# Smart_Umbrella.net
KiCad netlist of a schematic drawn in Altium Designer
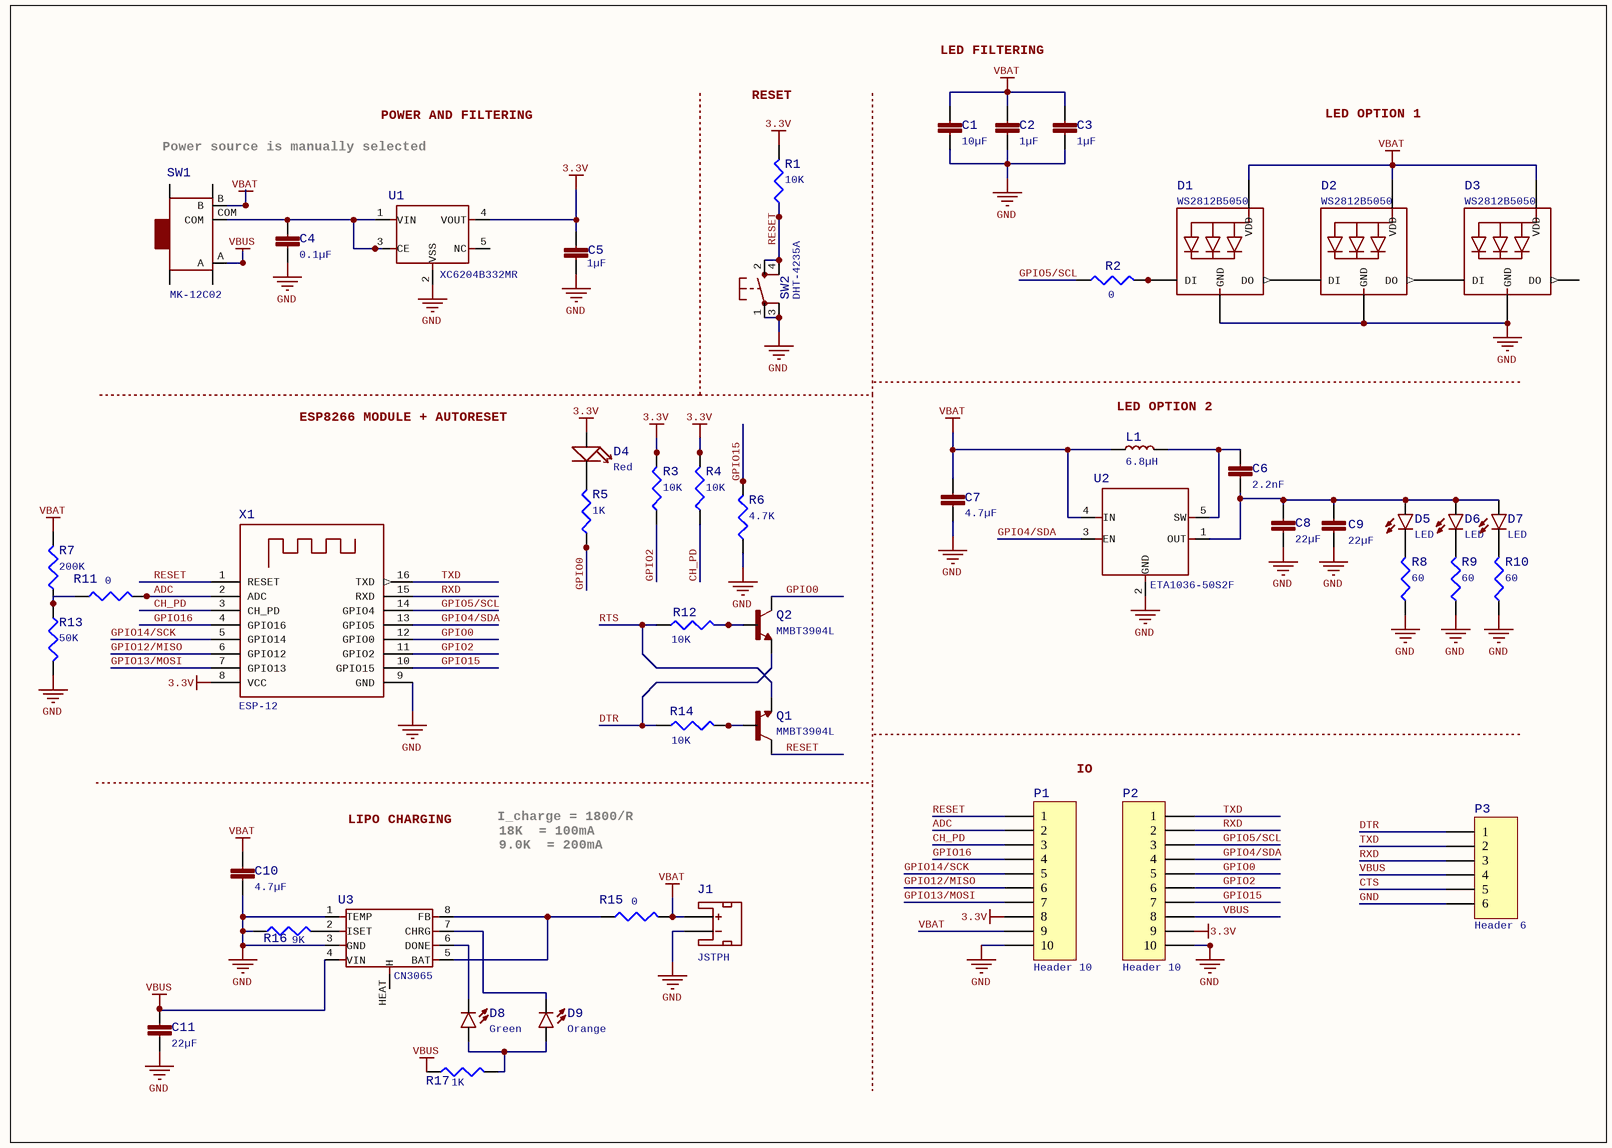
[diagram p0: Smart_Umbrella.SchDoc]

(export (version "E")
  (design (tool "Eeschema 10.0.6"))
  (components
    (comp (ref "C1")
      (value "10µF")
      (footprint "0805")
      (libsource (lib "SparkFun-Capacitors") (part "10UF-0805-10V-10%"))
    )
    (comp (ref "C2")
      (value "1µF")
      (footprint "0603")
      (libsource (lib "SparkFun-Capacitors") (part "1.0UF-0603-16V-10%"))
    )
    (comp (ref "C3")
      (value "1µF")
      (footprint "0603")
      (libsource (lib "SparkFun-Capacitors") (part "1.0UF-0603-16V-10%"))
    )
    (comp (ref "C4")
      (value "0.1µF")
      (footprint "0805")
      (libsource (lib "SparkFun-Capacitors") (part "10UF-0805-10V-10%"))
    )
    (comp (ref "C5")
      (value "1µF")
      (footprint "0603")
      (libsource (lib "SparkFun-Capacitors") (part "1.0UF-0603-16V-10%"))
    )
    (comp (ref "C6")
      (value "2.2nF")
      (footprint "0603")
      (libsource (lib "SparkFun-Capacitors") (part "1.0UF-0603-16V-10%"))
    )
    (comp (ref "C7")
      (value "4.7µF")
      (footprint "0805")
      (libsource (lib "SparkFun-Capacitors") (part "10UF-0805-10V-10%"))
    )
    (comp (ref "C8")
      (value "22µF")
      (footprint "0805")
      (libsource (lib "SparkFun-Capacitors") (part "10UF-0805-10V-10%"))
    )
    (comp (ref "C9")
      (value "22µF")
      (footprint "0805")
      (libsource (lib "SparkFun-Capacitors") (part "10UF-0805-10V-10%"))
    )
    (comp (ref "C10")
      (value "4.7µF")
      (footprint "0805")
      (libsource (lib "SparkFun-Capacitors") (part "10UF-0805-10V-10%"))
    )
    (comp (ref "C11")
      (value "22µF")
      (footprint "0805")
      (libsource (lib "SparkFun-Capacitors") (part "10UF-0805-10V-10%"))
    )
    (comp (ref "D1")
      (value "WS2812B5050")
      (footprint "WS2812B")
      (libsource (lib "adafruit") (part "WS2812B5050"))
    )
    (comp (ref "D2")
      (value "WS2812B5050")
      (footprint "WS2812B")
      (libsource (lib "adafruit") (part "WS2812B5050"))
    )
    (comp (ref "D3")
      (value "WS2812B5050")
      (footprint "WS2812B")
      (libsource (lib "adafruit") (part "WS2812B5050"))
    )
    (comp (ref "D4") (value "Red") (footprint "LED-0603") (libsource (lib "Discrete") (part "LED-0603")))
    (comp (ref "D5") (value "LED") (footprint "LED_5MM") (libsource (lib "SparkFun-LED") (part "LED5MM")))
    (comp (ref "D6") (value "LED") (footprint "LED_5MM") (libsource (lib "SparkFun-LED") (part "LED5MM")))
    (comp (ref "D7") (value "LED") (footprint "LED_5MM") (libsource (lib "SparkFun-LED") (part "LED5MM")))
    (comp (ref "D8")
      (value "Green")
      (footprint "LED-0603")
      (libsource (lib "SparkFun-LED") (part "LED-RED0603"))
    )
    (comp (ref "D9")
      (value "Orange")
      (footprint "LED-0603")
      (libsource (lib "SparkFun-LED") (part "LED-RED0603"))
    )
    (comp (ref "J1")
      (value "JSTPH")
      (footprint "JST-2-SMD")
      (libsource (lib "SparkFun-Connectors") (part "JST_2MM_MALE"))
    )
    (comp (ref "L1")
      (value "6.8µH")
      (footprint "L0603")
      (libsource (lib "Discrete") (part "INDUCTOR/FERRITE-BEAD-0603"))
    )
    (comp (ref "P1")
      (value "Header 10")
      (footprint "HDR1X10")
      (description "Header, 10-Pin")
      (fields (field (name "PUBLISHER") "Altium Limited"))
      (libsource (lib "Miscellaneous Connectors") (part "Header 10"))
    )
    (comp (ref "P2")
      (value "Header 10")
      (footprint "HDR1X10")
      (description "Header, 10-Pin")
      (fields (field (name "PUBLISHER") "Altium Limited"))
      (libsource (lib "") (part "Header 10_1"))
    )
    (comp (ref "P3")
      (value "Header 6")
      (footprint "HDR1X6")
      (description "Header, 6-Pin")
      (fields (field (name "PUBLISHER") "Altium Limited"))
      (libsource (lib "Miscellaneous Connectors") (part "Header 6"))
    )
    (comp (ref "Q1")
      (value "MMBT3904L")
      (footprint "SOT23-3")
      (fields (field (name "DRAWN") "KTOWN"))
      (libsource (lib "SparkFun") (part "TRANSISTOR_NPNSOT23-3"))
    )
    (comp (ref "Q2")
      (value "MMBT3904L")
      (footprint "SOT23-3")
      (fields (field (name "DRAWN") "KTOWN"))
      (libsource (lib "") (part "TRANSISTOR_NPNSOT23-3_1"))
    )
    (comp (ref "R1")
      (value "10K")
      (footprint "J1-0603")
      (description "Resistor")
      (fields (field (name "Comment") "Res3") (field (name "PUBLISHER") "Altium Limited"))
      (libsource (lib "Miscellaneous Devices") (part "Res3"))
    )
    (comp (ref "R2")
      (value "0")
      (footprint "J1-0603")
      (description "Resistor")
      (fields (field (name "Comment") "Res3") (field (name "PUBLISHER") "Altium Limited"))
      (libsource (lib "Miscellaneous Devices") (part "Res3"))
    )
    (comp (ref "R3")
      (value "10K")
      (footprint "J1-0603")
      (description "Resistor")
      (fields (field (name "Comment") "Res3") (field (name "PUBLISHER") "Altium Limited"))
      (libsource (lib "Miscellaneous Devices") (part "Res3"))
    )
    (comp (ref "R4")
      (value "10K")
      (footprint "J1-0603")
      (description "Resistor")
      (fields (field (name "Comment") "Res3") (field (name "PUBLISHER") "Altium Limited"))
      (libsource (lib "Miscellaneous Devices") (part "Res3"))
    )
    (comp (ref "R5")
      (value "1K")
      (footprint "J1-0603")
      (description "Resistor")
      (fields (field (name "Comment") "Res3") (field (name "PUBLISHER") "Altium Limited"))
      (libsource (lib "Miscellaneous Devices") (part "Res3"))
    )
    (comp (ref "R6")
      (value "4.7K")
      (footprint "J1-0603")
      (description "Resistor")
      (fields (field (name "Comment") "Res3") (field (name "PUBLISHER") "Altium Limited"))
      (libsource (lib "Miscellaneous Devices") (part "Res3"))
    )
    (comp (ref "R7")
      (value "200K")
      (footprint "J1-0603")
      (description "Resistor")
      (fields (field (name "Comment") "Res3") (field (name "PUBLISHER") "Altium Limited"))
      (libsource (lib "Miscellaneous Devices") (part "Res3"))
    )
    (comp (ref "R8")
      (value "60")
      (footprint "J1-0603")
      (description "Resistor")
      (fields (field (name "Comment") "Res3") (field (name "PUBLISHER") "Altium Limited"))
      (libsource (lib "Miscellaneous Devices") (part "Res3"))
    )
    (comp (ref "R9")
      (value "60")
      (footprint "J1-0603")
      (description "Resistor")
      (fields (field (name "Comment") "Res3") (field (name "PUBLISHER") "Altium Limited"))
      (libsource (lib "Miscellaneous Devices") (part "Res3"))
    )
    (comp (ref "R10")
      (value "60")
      (footprint "J1-0603")
      (description "Resistor")
      (fields (field (name "Comment") "Res3") (field (name "PUBLISHER") "Altium Limited"))
      (libsource (lib "Miscellaneous Devices") (part "Res3"))
    )
    (comp (ref "R11")
      (value "0")
      (footprint "J1-0603")
      (description "Resistor")
      (fields (field (name "Comment") "Res3") (field (name "PUBLISHER") "Altium Limited"))
      (libsource (lib "Miscellaneous Devices") (part "Res3"))
    )
    (comp (ref "R12")
      (value "10K")
      (footprint "J1-0603")
      (description "Resistor")
      (fields (field (name "Comment") "Res3") (field (name "PUBLISHER") "Altium Limited"))
      (libsource (lib "Miscellaneous Devices") (part "Res3"))
    )
    (comp (ref "R13")
      (value "50K")
      (footprint "J1-0603")
      (description "Resistor")
      (fields (field (name "Comment") "Res3") (field (name "PUBLISHER") "Altium Limited"))
      (libsource (lib "Miscellaneous Devices") (part "Res3"))
    )
    (comp (ref "R14")
      (value "10K")
      (footprint "J1-0603")
      (description "Resistor")
      (fields (field (name "Comment") "Res3") (field (name "PUBLISHER") "Altium Limited"))
      (libsource (lib "Miscellaneous Devices") (part "Res3"))
    )
    (comp (ref "R15")
      (value "0")
      (footprint "J1-0603")
      (description "Resistor")
      (fields (field (name "Comment") "Res3") (field (name "PUBLISHER") "Altium Limited"))
      (libsource (lib "Miscellaneous Devices") (part "Res3"))
    )
    (comp (ref "R16")
      (value "9K")
      (footprint "J1-0603")
      (description "Resistor")
      (fields (field (name "Comment") "Res3") (field (name "PUBLISHER") "Altium Limited"))
      (libsource (lib "Miscellaneous Devices") (part "Res3"))
    )
    (comp (ref "R17")
      (value "1K")
      (footprint "J1-0603")
      (description "Resistor")
      (fields (field (name "Comment") "Res3") (field (name "PUBLISHER") "Altium Limited"))
      (libsource (lib "Miscellaneous Devices") (part "Res3"))
    )
    (comp (ref "SW1")
      (value "MK-12C02")
      (footprint "SW7-SMD-L6.7X2.7X3.2MM")
      (libsource (lib "Seeed-OPL-Button") (part "SMD-TOGGLE-SWITCH-ON-ON(3+4P-6.7X2.7MM)"))
    )
    (comp (ref "SW2")
      (value "DHT-4235A")
      (footprint "KMR2")
      (libsource (lib "adafruit") (part "SPST_TACT-KMR2"))
    )
    (comp (ref "U1")
      (value "XC6204B332MR")
      (footprint "SOT-23-5")
      (libsource (lib "Seeed-OPL-ic") (part "PMIC-LDO-XC6204B332MR(SOT23-5)"))
    )
    (comp (ref "U2")
      (value "ETA1036-50S2F")
      (footprint "SOT-23-5")
      (fields (field (name "MPN") "ETA1036-50S2F-T"))
      (libsource (lib "Seeed-OPL-ic") (part "PMIC-ETA1036-50S2F-T(SOT23-5)"))
    )
    (comp (ref "U3")
      (value "CN3065")
      (footprint "DFN8G-0.5-3X3MM")
      (libsource (lib "Seeed-OPL-ic") (part "PMIC-CN3065(DFN8)"))
    )
    (comp (ref "X1") (value "ESP-12") (footprint "ESP-12") (libsource (lib "adafruit") (part "ESP-12")))
  )
  (nets
    (net (code "1") (name "/ADC") (class "Default")
      (node (ref "P1") (pin "2") (pinfunction "2_2") (pintype "passive"))
      (node (ref "R11") (pin "2") (pinfunction "2_2") (pintype "passive"))
      (node (ref "X1") (pin "2") (pinfunction "ADC_2") (pintype "passive"))
    )
    (net (code "2") (name "/CH_PD") (class "Default")
      (node (ref "P1") (pin "3") (pinfunction "3_3") (pintype "passive"))
      (node (ref "R4") (pin "1") (pinfunction "1_1") (pintype "passive"))
      (node (ref "X1") (pin "3") (pinfunction "CH_PD_3") (pintype "passive"))
    )
    (net (code "3") (name "/CTS") (class "Default")
      (node (ref "P3") (pin "5") (pinfunction "5_5") (pintype "passive"))
    )
    (net (code "4") (name "/DTR") (class "Default")
      (node (ref "P3") (pin "1") (pinfunction "1_1") (pintype "passive"))
      (node (ref "Q2") (pin "2") (pinfunction "E_2") (pintype "passive"))
      (node (ref "R14") (pin "1") (pinfunction "1_1") (pintype "passive"))
    )
    (net (code "5") (name "/GPIO0") (class "Default")
      (node (ref "P2") (pin "5") (pinfunction "5_5") (pintype "passive"))
      (node (ref "Q2") (pin "3") (pinfunction "C_3") (pintype "passive"))
      (node (ref "R5") (pin "1") (pinfunction "1_1") (pintype "passive"))
      (node (ref "X1") (pin "12") (pinfunction "GPIO0_12") (pintype "passive"))
    )
    (net (code "6") (name "/GPIO2") (class "Default")
      (node (ref "P2") (pin "6") (pinfunction "6_6") (pintype "passive"))
      (node (ref "R3") (pin "1") (pinfunction "1_1") (pintype "passive"))
      (node (ref "X1") (pin "11") (pinfunction "GPIO2_11") (pintype "passive"))
    )
    (net (code "7") (name "/GPIO4{slash}SDA") (class "Default")
      (node (ref "P2") (pin "4") (pinfunction "4_4") (pintype "passive"))
      (node (ref "U2") (pin "3") (pinfunction "EN_3") (pintype "passive"))
      (node (ref "X1") (pin "13") (pinfunction "GPIO5_13") (pintype "passive"))
    )
    (net (code "8") (name "/GPIO5{slash}SCL") (class "Default")
      (node (ref "P2") (pin "3") (pinfunction "3_3") (pintype "passive"))
      (node (ref "R2") (pin "1") (pinfunction "1_1") (pintype "passive"))
      (node (ref "X1") (pin "14") (pinfunction "GPIO4_14") (pintype "passive"))
    )
    (net (code "9") (name "/GPIO12{slash}MISO") (class "Default")
      (node (ref "P1") (pin "6") (pinfunction "6_6") (pintype "passive"))
      (node (ref "X1") (pin "6") (pinfunction "GPIO12_6") (pintype "passive"))
    )
    (net (code "10") (name "/GPIO13{slash}MOSI") (class "Default")
      (node (ref "P1") (pin "7") (pinfunction "7_7") (pintype "passive"))
      (node (ref "X1") (pin "7") (pinfunction "GPIO13_7") (pintype "passive"))
    )
    (net (code "11") (name "/GPIO14{slash}SCK") (class "Default")
      (node (ref "P1") (pin "5") (pinfunction "5_5") (pintype "passive"))
      (node (ref "X1") (pin "5") (pinfunction "GPIO14_5") (pintype "passive"))
    )
    (net (code "12") (name "/GPIO15") (class "Default")
      (node (ref "P2") (pin "7") (pinfunction "7_7") (pintype "passive"))
      (node (ref "R6") (pin "2") (pinfunction "2_2") (pintype "passive"))
      (node (ref "X1") (pin "10") (pinfunction "GPIO15_10") (pintype "passive"))
    )
    (net (code "13") (name "/GPIO16") (class "Default")
      (node (ref "P1") (pin "4") (pinfunction "4_4") (pintype "passive"))
      (node (ref "X1") (pin "4") (pinfunction "GPIO16_4") (pintype "passive"))
    )
    (net (code "14") (name "/RESET") (class "Default")
      (node (ref "P1") (pin "1") (pinfunction "1_1") (pintype "passive"))
      (node (ref "Q1") (pin "3") (pinfunction "C_3") (pintype "passive"))
      (node (ref "R1") (pin "1") (pinfunction "1_1") (pintype "passive"))
      (node (ref "SW2") (pin "2") (pinfunction "S_2") (pintype "passive"))
      (node (ref "SW2") (pin "4") (pinfunction "S1_4") (pintype "passive"))
      (node (ref "X1") (pin "1") (pinfunction "RESET_1") (pintype "passive"))
    )
    (net (code "15") (name "/RTS") (class "Default")
      (node (ref "Q1") (pin "2") (pinfunction "E_2") (pintype "passive"))
      (node (ref "R12") (pin "1") (pinfunction "1_1") (pintype "passive"))
    )
    (net (code "16") (name "/RXD") (class "Default")
      (node (ref "P2") (pin "2") (pinfunction "2_2") (pintype "passive"))
      (node (ref "P3") (pin "3") (pinfunction "3_3") (pintype "passive"))
      (node (ref "X1") (pin "15") (pinfunction "RXD_15") (pintype "passive"))
    )
    (net (code "17") (name "/TXD") (class "Default")
      (node (ref "P2") (pin "1") (pinfunction "1_1") (pintype "passive"))
      (node (ref "P3") (pin "2") (pinfunction "2_2") (pintype "passive"))
      (node (ref "X1") (pin "16") (pinfunction "TXD_16") (pintype "output"))
    )
    (net (code "18") (name "3.3V") (class "Default")
      (node (ref "C5") (pin "1") (pinfunction "1_1") (pintype "passive"))
      (node (ref "D4") (pin "+") (pinfunction "+_+") (pintype "passive"))
      (node (ref "P1") (pin "8") (pinfunction "8_8") (pintype "passive"))
      (node (ref "P2") (pin "9") (pinfunction "9_9") (pintype "passive"))
      (node (ref "R1") (pin "2") (pinfunction "2_2") (pintype "passive"))
      (node (ref "R3") (pin "2") (pinfunction "2_2") (pintype "passive"))
      (node (ref "R4") (pin "2") (pinfunction "2_2") (pintype "passive"))
      (node (ref "U1") (pin "4") (pinfunction "VOUT_4") (pintype "power_in"))
      (node (ref "X1") (pin "8") (pinfunction "VCC_8") (pintype "power_in"))
    )
    (net (code "19") (name "GND") (class "Default")
      (node (ref "C1") (pin "2") (pinfunction "2_2") (pintype "passive"))
      (node (ref "C10") (pin "2") (pinfunction "2_2") (pintype "passive"))
      (node (ref "C11") (pin "2") (pinfunction "2_2") (pintype "passive"))
      (node (ref "C2") (pin "2") (pinfunction "2_2") (pintype "passive"))
      (node (ref "C3") (pin "2") (pinfunction "2_2") (pintype "passive"))
      (node (ref "C4") (pin "2") (pinfunction "2_2") (pintype "passive"))
      (node (ref "C5") (pin "2") (pinfunction "2_2") (pintype "passive"))
      (node (ref "C7") (pin "2") (pinfunction "2_2") (pintype "passive"))
      (node (ref "C8") (pin "2") (pinfunction "2_2") (pintype "passive"))
      (node (ref "C9") (pin "2") (pinfunction "2_2") (pintype "passive"))
      (node (ref "D1") (pin "3-GND") (pinfunction "GND_3-GND") (pintype "power_in"))
      (node (ref "D2") (pin "3-GND") (pinfunction "GND_3-GND") (pintype "power_in"))
      (node (ref "D3") (pin "3-GND") (pinfunction "GND_3-GND") (pintype "power_in"))
      (node (ref "J1") (pin "1") (pinfunction "-_1") (pintype "passive"))
      (node (ref "P1") (pin "10") (pinfunction "10_10") (pintype "passive"))
      (node (ref "P2") (pin "10") (pinfunction "10_10") (pintype "passive"))
      (node (ref "P3") (pin "6") (pinfunction "6_6") (pintype "passive"))
      (node (ref "R10") (pin "1") (pinfunction "1_1") (pintype "passive"))
      (node (ref "R13") (pin "2") (pinfunction "2_2") (pintype "passive"))
      (node (ref "R16") (pin "1") (pinfunction "1_1") (pintype "passive"))
      (node (ref "R6") (pin "1") (pinfunction "1_1") (pintype "passive"))
      (node (ref "R8") (pin "1") (pinfunction "1_1") (pintype "passive"))
      (node (ref "R9") (pin "1") (pinfunction "1_1") (pintype "passive"))
      (node (ref "SW2") (pin "1") (pinfunction "P_1") (pintype "passive"))
      (node (ref "SW2") (pin "3") (pinfunction "P1_3") (pintype "passive"))
      (node (ref "U1") (pin "2") (pinfunction "VSS_2") (pintype "power_in"))
      (node (ref "U2") (pin "2") (pinfunction "GND_2") (pintype "passive"))
      (node (ref "U3") (pin "1") (pinfunction "TEMP_1") (pintype "passive"))
      (node (ref "U3") (pin "3") (pinfunction "GND_3") (pintype "power_in"))
      (node (ref "X1") (pin "9") (pinfunction "GND_9") (pintype "power_in"))
    )
    (net (code "20") (name "Net-(D1-DI)") (class "Default")
      (node (ref "D1") (pin "4-DIN") (pinfunction "DI_4-DIN") (pintype "passive"))
      (node (ref "R2") (pin "2") (pinfunction "2_2") (pintype "passive"))
    )
    (net (code "21") (name "Net-(D1-DO)") (class "Default")
      (node (ref "D1") (pin "2-DOUT") (pinfunction "DO_2-DOUT") (pintype "output"))
      (node (ref "D2") (pin "4-DIN") (pinfunction "DI_4-DIN") (pintype "passive"))
    )
    (net (code "22") (name "Net-(D2-DO)") (class "Default")
      (node (ref "D2") (pin "2-DOUT") (pinfunction "DO_2-DOUT") (pintype "output"))
      (node (ref "D3") (pin "4-DIN") (pinfunction "DI_4-DIN") (pintype "passive"))
    )
    (net (code "23") (name "Net-(D4-Pad-)") (class "Default")
      (node (ref "D4") (pin "-") (pinfunction "-_-") (pintype "passive"))
      (node (ref "R5") (pin "2") (pinfunction "2_2") (pintype "passive"))
    )
    (net (code "24") (name "Net-(D5-C)") (class "Default")
      (node (ref "D5") (pin "K") (pinfunction "C_K") (pintype "passive"))
      (node (ref "R8") (pin "2") (pinfunction "2_2") (pintype "passive"))
    )
    (net (code "25") (name "Net-(D6-C)") (class "Default")
      (node (ref "D6") (pin "K") (pinfunction "C_K") (pintype "passive"))
      (node (ref "R9") (pin "2") (pinfunction "2_2") (pintype "passive"))
    )
    (net (code "26") (name "Net-(D7-C)") (class "Default")
      (node (ref "D7") (pin "K") (pinfunction "C_K") (pintype "passive"))
      (node (ref "R10") (pin "2") (pinfunction "2_2") (pintype "passive"))
    )
    (net (code "27") (name "Net-(D8-PadA)") (class "Default")
      (node (ref "D8") (pin "A") (pinfunction "A_A") (pintype "passive"))
      (node (ref "D9") (pin "A") (pinfunction "A_A") (pintype "passive"))
      (node (ref "R17") (pin "2") (pinfunction "2_2") (pintype "passive"))
    )
    (net (code "28") (name "Net-(Q1-B)") (class "Default")
      (node (ref "Q1") (pin "1") (pinfunction "B_1") (pintype "passive"))
      (node (ref "R14") (pin "2") (pinfunction "2_2") (pintype "passive"))
    )
    (net (code "29") (name "Net-(Q2-B)") (class "Default")
      (node (ref "Q2") (pin "1") (pinfunction "B_1") (pintype "passive"))
      (node (ref "R12") (pin "2") (pinfunction "2_2") (pintype "passive"))
    )
    (net (code "30") (name "Net-(R11-Pad1)") (class "Default")
      (node (ref "R11") (pin "1") (pinfunction "1_1") (pintype "passive"))
      (node (ref "R13") (pin "1") (pinfunction "1_1") (pintype "passive"))
      (node (ref "R7") (pin "1") (pinfunction "1_1") (pintype "passive"))
    )
    (net (code "31") (name "Net-(U1-CE)") (class "Default")
      (node (ref "C4") (pin "1") (pinfunction "1_1") (pintype "passive"))
      (node (ref "SW1") (pin "COM") (pinfunction "COM_COM") (pintype "passive"))
      (node (ref "U1") (pin "1") (pinfunction "VIN_1") (pintype "passive"))
      (node (ref "U1") (pin "3") (pinfunction "CE_3") (pintype "passive"))
    )
    (net (code "32") (name "Net-(U2-OUT)") (class "Default")
      (node (ref "C6") (pin "2") (pinfunction "2_2") (pintype "passive"))
      (node (ref "C8") (pin "1") (pinfunction "1_1") (pintype "passive"))
      (node (ref "C9") (pin "1") (pinfunction "1_1") (pintype "passive"))
      (node (ref "D5") (pin "A") (pinfunction "A_A") (pintype "passive"))
      (node (ref "D6") (pin "A") (pinfunction "A_A") (pintype "passive"))
      (node (ref "D7") (pin "A") (pinfunction "A_A") (pintype "passive"))
      (node (ref "U2") (pin "1") (pinfunction "OUT_1") (pintype "passive"))
    )
    (net (code "33") (name "Net-(U2-SW)") (class "Default")
      (node (ref "C6") (pin "1") (pinfunction "1_1") (pintype "passive"))
      (node (ref "L1") (pin "2") (pinfunction "2_2") (pintype "passive"))
      (node (ref "U2") (pin "5") (pinfunction "SW_5") (pintype "passive"))
    )
    (net (code "34") (name "Net-(U3-BAT)") (class "Default")
      (node (ref "R15") (pin "1") (pinfunction "1_1") (pintype "passive"))
      (node (ref "U3") (pin "5") (pinfunction "BAT_5") (pintype "passive"))
      (node (ref "U3") (pin "8") (pinfunction "FB_8") (pintype "passive"))
    )
    (net (code "35") (name "Net-(U3-CHRG)") (class "Default")
      (node (ref "D9") (pin "C") (pinfunction "C_C") (pintype "passive"))
      (node (ref "U3") (pin "7") (pinfunction "CHRG_7") (pintype "passive"))
    )
    (net (code "36") (name "Net-(U3-DONE)") (class "Default")
      (node (ref "D8") (pin "C") (pinfunction "C_C") (pintype "passive"))
      (node (ref "U3") (pin "6") (pinfunction "DONE_6") (pintype "passive"))
    )
    (net (code "37") (name "Net-(U3-ISET)") (class "Default")
      (node (ref "R16") (pin "2") (pinfunction "2_2") (pintype "passive"))
      (node (ref "U3") (pin "2") (pinfunction "ISET_2") (pintype "passive"))
    )
    (net (code "38") (name "VBAT") (class "Default")
      (node (ref "C1") (pin "1") (pinfunction "1_1") (pintype "passive"))
      (node (ref "C10") (pin "1") (pinfunction "1_1") (pintype "passive"))
      (node (ref "C2") (pin "1") (pinfunction "1_1") (pintype "passive"))
      (node (ref "C3") (pin "1") (pinfunction "1_1") (pintype "passive"))
      (node (ref "C7") (pin "1") (pinfunction "1_1") (pintype "passive"))
      (node (ref "D1") (pin "1-VDD") (pinfunction "VDD_1-VDD") (pintype "power_in"))
      (node (ref "D2") (pin "1-VDD") (pinfunction "VDD_1-VDD") (pintype "power_in"))
      (node (ref "D3") (pin "1-VDD") (pinfunction "VDD_1-VDD") (pintype "power_in"))
      (node (ref "J1") (pin "2") (pinfunction "+_2") (pintype "passive"))
      (node (ref "L1") (pin "1") (pinfunction "1_1") (pintype "passive"))
      (node (ref "P1") (pin "9") (pinfunction "9_9") (pintype "passive"))
      (node (ref "R15") (pin "2") (pinfunction "2_2") (pintype "passive"))
      (node (ref "R7") (pin "2") (pinfunction "2_2") (pintype "passive"))
      (node (ref "SW1") (pin "B") (pinfunction "B_B") (pintype "passive"))
      (node (ref "U2") (pin "4") (pinfunction "IN_4") (pintype "passive"))
    )
    (net (code "39") (name "VBUS") (class "Default")
      (node (ref "C11") (pin "1") (pinfunction "1_1") (pintype "passive"))
      (node (ref "P2") (pin "8") (pinfunction "8_8") (pintype "passive"))
      (node (ref "P3") (pin "4") (pinfunction "4_4") (pintype "passive"))
      (node (ref "R17") (pin "1") (pinfunction "1_1") (pintype "passive"))
      (node (ref "SW1") (pin "A") (pinfunction "A_A") (pintype "passive"))
      (node (ref "U3") (pin "4") (pinfunction "VIN_4") (pintype "passive"))
    )
    (net (code "40") (name "unconnected-(D3-DO-Pad2-DOUT)") (class "Default")
      (node (ref "D3") (pin "2-DOUT") (pinfunction "DO_2-DOUT") (pintype "output"))
    )
    (net (code "41") (name "unconnected-(J1-PAD1-PadNC1)") (class "Default")
      (node (ref "J1") (pin "NC1") (pinfunction "PAD1_NC1") (pintype "passive"))
    )
    (net (code "42") (name "unconnected-(J1-PAD2-PadNC2)") (class "Default")
      (node (ref "J1") (pin "NC2") (pinfunction "PAD2_NC2") (pintype "passive"))
    )
    (net (code "43") (name "unconnected-(SW1-PadSS1)") (class "Default")
      (node (ref "SW1") (pin "SS1") (pinfunction "SS1_SS1") (pintype "passive"))
    )
    (net (code "44") (name "unconnected-(SW1-PadSS2)") (class "Default")
      (node (ref "SW1") (pin "SS2") (pinfunction "SS2_SS2") (pintype "passive"))
    )
    (net (code "45") (name "unconnected-(SW1-PadSS3)") (class "Default")
      (node (ref "SW1") (pin "SS3") (pinfunction "SS3_SS3") (pintype "passive"))
    )
    (net (code "46") (name "unconnected-(SW1-PadSS4)") (class "Default")
      (node (ref "SW1") (pin "SS4") (pinfunction "SS4_SS4") (pintype "passive"))
    )
    (net (code "47") (name "unconnected-(U1-NC-Pad5)") (class "Default")
      (node (ref "U1") (pin "5") (pinfunction "NC_5") (pintype "passive"))
    )
    (net (code "48") (name "unconnected-(U3-H-PadHEAT)") (class "Default")
      (node (ref "U3") (pin "HEAT") (pinfunction "H_HEAT") (pintype "passive"))
    )
  )
)
